# LO_tap.net
KiCad netlist of a schematic drawn in Altium Designer
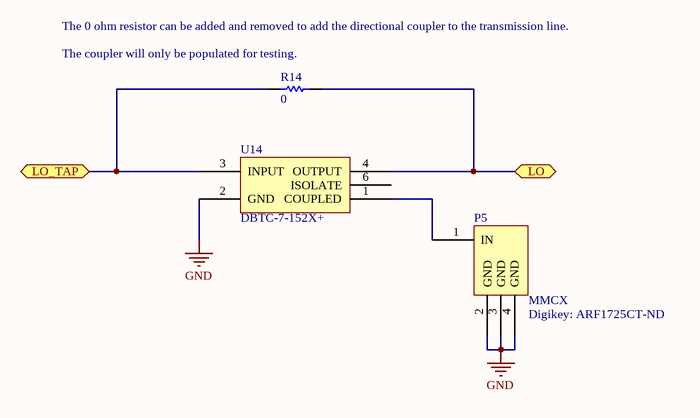
[diagram p0: LO_tap.SchDoc]

(export (version "E")
  (design (tool "Eeschema 10.0.6"))
  (components
    (comp (ref "P5") (value "MMCX") (libsource (lib "shield_components") (part "MMCX")))
    (comp (ref "R14")
      (value "0")
      (footprint "0402")
      (description "Semiconductor Resistor")
      (fields (field (name "Comment") "Res Semi") (field (name "PUBLISHER") "Altium Limited"))
      (libsource (lib "Miscellaneous Devices") (part "Res Semi"))
    )
    (comp (ref "U14") (value "DBTC-7-152X+") (libsource (lib "shield_components") (part "DBTC-7-152X+")))
  )
  (nets
    (net (code "1") (name "/LO") (class "Default")
      (node (ref "R14") (pin "1") (pinfunction "1_1") (pintype "passive"))
      (node (ref "U14") (pin "4") (pinfunction "OUTPUT_4") (pintype "passive"))
    )
    (net (code "2") (name "/LO_TAP") (class "Default")
      (node (ref "R14") (pin "2") (pinfunction "2_2") (pintype "passive"))
      (node (ref "U14") (pin "3") (pinfunction "INPUT_3") (pintype "passive"))
    )
    (net (code "3") (name "GND") (class "Default")
      (node (ref "P5") (pin "2") (pinfunction "GND_2") (pintype "passive"))
      (node (ref "P5") (pin "3") (pinfunction "GND_3") (pintype "passive"))
      (node (ref "P5") (pin "4") (pinfunction "GND_4") (pintype "passive"))
      (node (ref "U14") (pin "2") (pinfunction "GND_2") (pintype "passive"))
    )
    (net (code "4") (name "Net-(P5-IN)") (class "Default")
      (node (ref "P5") (pin "1") (pinfunction "IN_1") (pintype "passive"))
      (node (ref "U14") (pin "1") (pinfunction "COUPLED_1") (pintype "passive"))
    )
    (net (code "5") (name "unconnected-(U14-ISOLATE-Pad6)") (class "Default")
      (node (ref "U14") (pin "6") (pinfunction "ISOLATE_6") (pintype "passive"))
    )
  )
)
